# NARTF.net
KiCad netlist of a schematic drawn in EAGLE
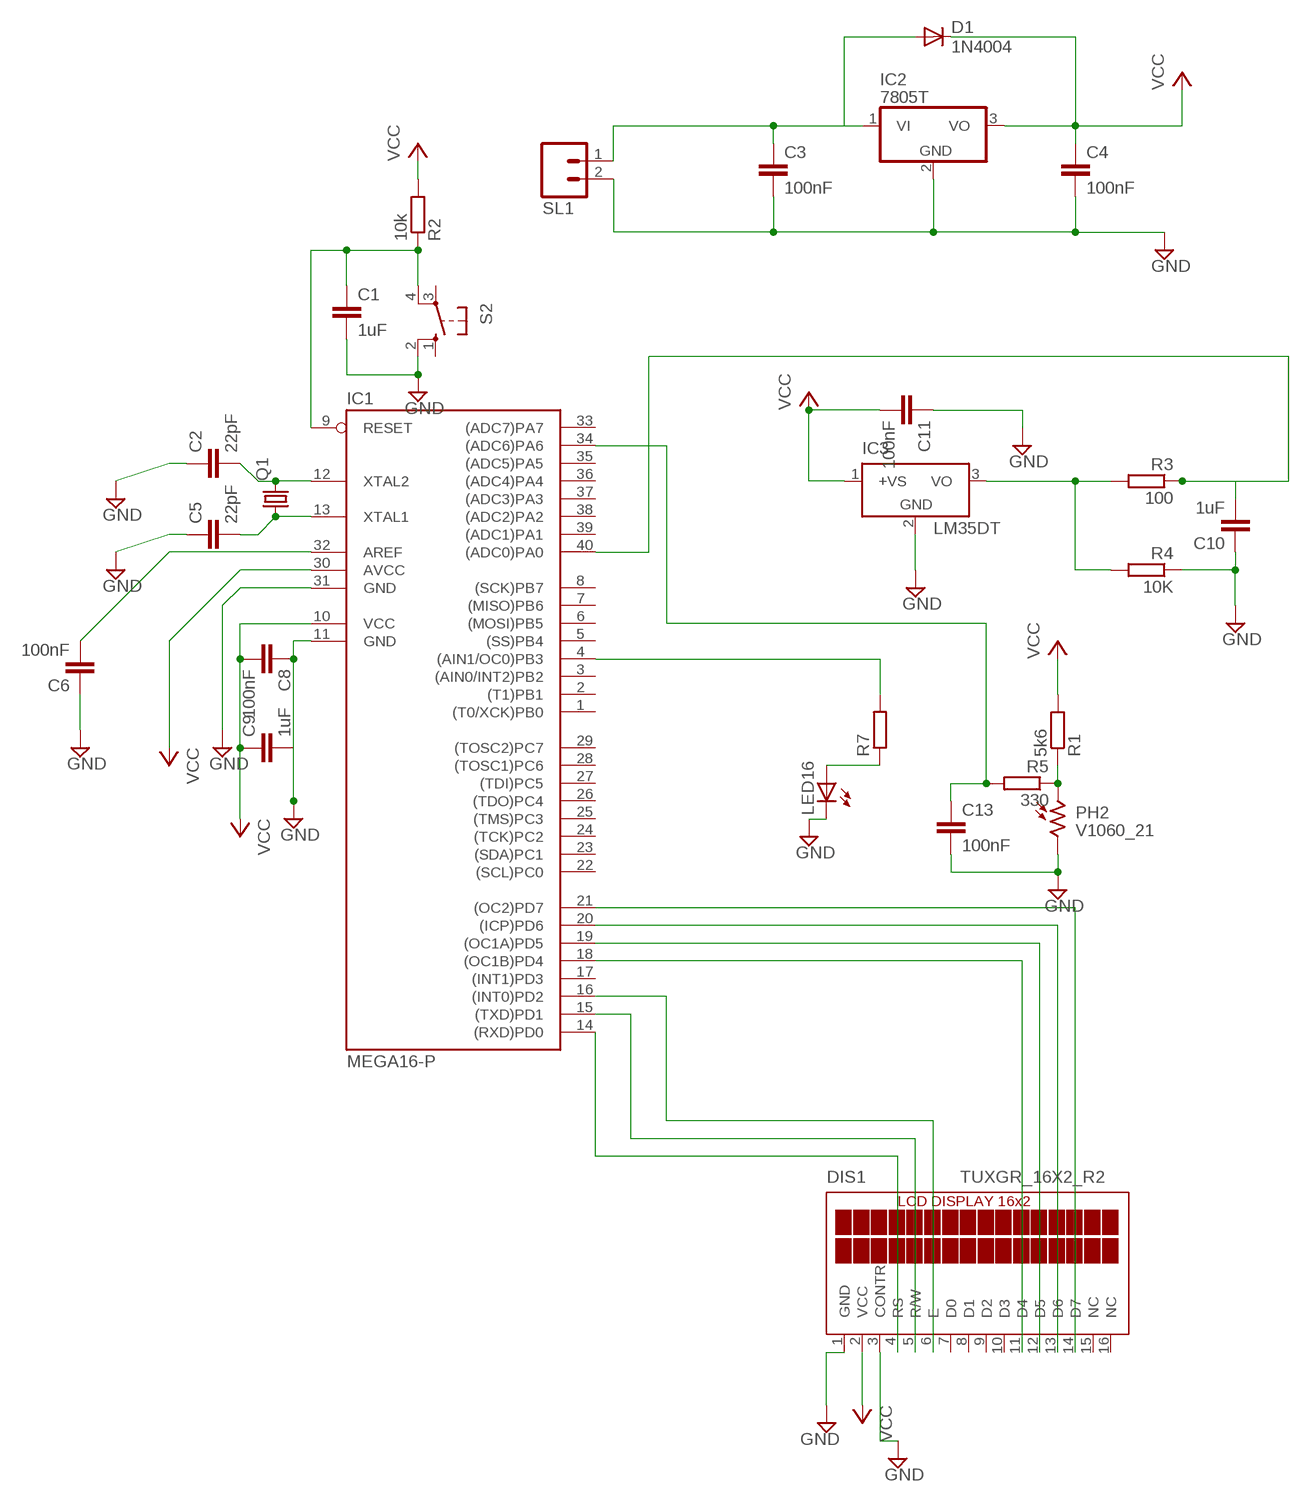
[diagram p0: schematic, sheet 1]

(export (version "E")
  (design (tool "Eeschema 10.0.6"))
  (components
    (comp (ref "C1")
      (value "1uF")
      (footprint "eagle-import:C025-025X050")
      (libsource (lib "eagle-import") (part "C-EU025-025X050"))
    )
    (comp (ref "C2")
      (value "22pF")
      (footprint "eagle-import:C025-025X050")
      (libsource (lib "eagle-import") (part "C-EU025-025X050"))
    )
    (comp (ref "C3")
      (value "100nF")
      (footprint "eagle-import:C025-025X050")
      (libsource (lib "eagle-import") (part "C-EU025-025X050"))
    )
    (comp (ref "C4")
      (value "100nF")
      (footprint "eagle-import:C025-025X050")
      (libsource (lib "eagle-import") (part "C-EU025-025X050"))
    )
    (comp (ref "C5")
      (value "22pF")
      (footprint "eagle-import:C025-025X050")
      (libsource (lib "eagle-import") (part "C-EU025-025X050"))
    )
    (comp (ref "C6")
      (value "100nF")
      (footprint "eagle-import:C025-025X050")
      (libsource (lib "eagle-import") (part "C-EU025-025X050"))
    )
    (comp (ref "C8")
      (value "100nF")
      (footprint "eagle-import:C025-025X050")
      (libsource (lib "eagle-import") (part "C-EU025-025X050"))
    )
    (comp (ref "C9")
      (value "1uF")
      (footprint "eagle-import:C025-025X050")
      (libsource (lib "eagle-import") (part "C-EU025-025X050"))
    )
    (comp (ref "C10")
      (value "1uF")
      (footprint "eagle-import:C025-025X050")
      (libsource (lib "eagle-import") (part "C-EU025-025X050"))
    )
    (comp (ref "C11")
      (value "100nF")
      (footprint "eagle-import:C025-025X050")
      (libsource (lib "eagle-import") (part "C-EU025-025X050"))
    )
    (comp (ref "C13")
      (value "100nF")
      (footprint "eagle-import:C025-025X050")
      (libsource (lib "eagle-import") (part "C-EU025-025X050"))
    )
    (comp (ref "D1")
      (value "1N4004")
      (footprint "eagle-import:DO41-10")
      (libsource (lib "eagle-import") (part "1N4004"))
    )
    (comp (ref "DIS1")
      (value "TUXGR_16X2_R2")
      (footprint "eagle-import:TUXGR_16X2_R2")
      (libsource (lib "eagle-import") (part "TUXGR_16X2_R2"))
    )
    (comp (ref "IC1")
      (value "MEGA16-P")
      (footprint "eagle-import:DIL40")
      (fields (field (name "MPN") "ATMEGA16-16PU"))
      (libsource (lib "eagle-import") (part "MEGA16-P"))
    )
    (comp (ref "IC2")
      (value "7805T")
      (footprint "eagle-import:TO220H")
      (libsource (lib "eagle-import") (part "78T05"))
    )
    (comp (ref "IC3")
      (value "LM35DT")
      (footprint "eagle-import:TO220V")
      (libsource (lib "eagle-import") (part "LM35DT"))
    )
    (comp (ref "LED16")
      (value "LED3MM")
      (footprint "eagle-import:LED3MM")
      (libsource (lib "eagle-import") (part "LED3MM"))
    )
    (comp (ref "PH2")
      (value "V1060_21")
      (footprint "eagle-import:TO-5_V10")
      (libsource (lib "eagle-import") (part "?1060V_21"))
    )
    (comp (ref "Q1")
      (value "CRYSTALHC49U70")
      (footprint "eagle-import:HC49U70")
      (libsource (lib "eagle-import") (part "CRYSTALHC49U70"))
    )
    (comp (ref "R1")
      (value "5k6")
      (footprint "eagle-import:0207_7")
      (libsource (lib "eagle-import") (part "R-EU_0207/7"))
    )
    (comp (ref "R2")
      (value "10k")
      (footprint "eagle-import:0207_7")
      (libsource (lib "eagle-import") (part "R-EU_0207/7"))
    )
    (comp (ref "R3")
      (value "100")
      (footprint "eagle-import:0207_7")
      (libsource (lib "eagle-import") (part "R-EU_0207/7"))
    )
    (comp (ref "R4")
      (value "10K")
      (footprint "eagle-import:0207_7")
      (libsource (lib "eagle-import") (part "R-EU_0207/7"))
    )
    (comp (ref "R5")
      (value "330")
      (footprint "eagle-import:0207_7")
      (libsource (lib "eagle-import") (part "R-EU_0207/7"))
    )
    (comp (ref "R7")
      (value "R-EU_0207/12")
      (footprint "eagle-import:0207_12")
      (libsource (lib "eagle-import") (part "rcl@1_R-EU_0207/12"))
    )
    (comp (ref "S2")
      (value "10-XX")
      (footprint "eagle-import:B3F-10XX")
      (fields (field (name "MPN") "B3F-1000"))
      (libsource (lib "eagle-import") (part "10-XX"))
    )
    (comp (ref "SL1")
      (value "M02")
      (footprint "eagle-import:02P")
      (libsource (lib "eagle-import") (part "M02"))
    )
  )
  (nets
    (net (code "1") (name "GND") (class "Default")
      (node (ref "C1") (pin "2") (pinfunction "2_2") (pintype "passive"))
      (node (ref "C10") (pin "1") (pinfunction "1_1") (pintype "passive"))
      (node (ref "C11") (pin "1") (pinfunction "1_1") (pintype "passive"))
      (node (ref "C13") (pin "2") (pinfunction "2_2") (pintype "passive"))
      (node (ref "C2") (pin "1") (pinfunction "1_1") (pintype "passive"))
      (node (ref "C3") (pin "2") (pinfunction "2_2") (pintype "passive"))
      (node (ref "C4") (pin "2") (pinfunction "2_2") (pintype "passive"))
      (node (ref "C5") (pin "1") (pinfunction "1_1") (pintype "passive"))
      (node (ref "C6") (pin "1") (pinfunction "1_1") (pintype "passive"))
      (node (ref "C8") (pin "1") (pinfunction "1_1") (pintype "passive"))
      (node (ref "C9") (pin "2") (pinfunction "2_2") (pintype "passive"))
      (node (ref "DIS1") (pin "1") (pinfunction "GND_1") (pintype "power_in"))
      (node (ref "DIS1") (pin "3") (pinfunction "CONTR_3") (pintype "input"))
      (node (ref "IC1") (pin "11") (pinfunction "GND_11") (pintype "power_in"))
      (node (ref "IC1") (pin "31") (pinfunction "GND_31") (pintype "power_in"))
      (node (ref "IC2") (pin "2") (pinfunction "GND_2") (pintype "passive"))
      (node (ref "IC3") (pin "2") (pinfunction "GND_2") (pintype "power_in"))
      (node (ref "LED16") (pin "K") (pinfunction "C_K") (pintype "passive"))
      (node (ref "PH2") (pin "2") (pinfunction "2_2") (pintype "passive"))
      (node (ref "R4") (pin "1") (pinfunction "1_1") (pintype "passive"))
      (node (ref "S2") (pin "2") (pinfunction "S1_2") (pintype "passive"))
      (node (ref "SL1") (pin "2") (pinfunction "2_2") (pintype "passive"))
    )
    (net (code "2") (name "Net-(DIS1-D4)") (class "Default")
      (node (ref "DIS1") (pin "11") (pinfunction "D4_11") (pintype "input"))
      (node (ref "IC1") (pin "18") (pinfunction "(OC1B)PD4_18") (pintype "bidirectional"))
    )
    (net (code "3") (name "Net-(DIS1-D5)") (class "Default")
      (node (ref "DIS1") (pin "12") (pinfunction "D5_12") (pintype "input"))
      (node (ref "IC1") (pin "19") (pinfunction "(OC1A)PD5_19") (pintype "bidirectional"))
    )
    (net (code "4") (name "Net-(DIS1-D6)") (class "Default")
      (node (ref "DIS1") (pin "13") (pinfunction "D6_13") (pintype "input"))
      (node (ref "IC1") (pin "20") (pinfunction "(ICP)PD6_20") (pintype "bidirectional"))
    )
    (net (code "5") (name "Net-(DIS1-D7)") (class "Default")
      (node (ref "DIS1") (pin "14") (pinfunction "D7_14") (pintype "input"))
      (node (ref "IC1") (pin "21") (pinfunction "(OC2)PD7_21") (pintype "bidirectional"))
    )
    (net (code "6") (name "Net-(DIS1-E)") (class "Default")
      (node (ref "DIS1") (pin "6") (pinfunction "E_6") (pintype "input"))
      (node (ref "IC1") (pin "16") (pinfunction "(INT0)PD2_16") (pintype "bidirectional"))
    )
    (net (code "7") (name "Net-(DIS1-RS)") (class "Default")
      (node (ref "DIS1") (pin "4") (pinfunction "RS_4") (pintype "input"))
      (node (ref "IC1") (pin "14") (pinfunction "(RXD)PD0_14") (pintype "bidirectional"))
    )
    (net (code "8") (name "Net-(DIS1-R{slash}W)") (class "Default")
      (node (ref "DIS1") (pin "5") (pinfunction "R/W_5") (pintype "input"))
      (node (ref "IC1") (pin "15") (pinfunction "(TXD)PD1_15") (pintype "bidirectional"))
    )
    (net (code "9") (name "Net-(IC1-(ADC0)PA0)") (class "Default")
      (node (ref "C10") (pin "2") (pinfunction "2_2") (pintype "passive"))
      (node (ref "IC1") (pin "40") (pinfunction "(ADC0)PA0_40") (pintype "bidirectional"))
      (node (ref "R3") (pin "1") (pinfunction "1_1") (pintype "passive"))
    )
    (net (code "10") (name "Net-(IC1-(ADC6)PA6)") (class "Default")
      (node (ref "C13") (pin "1") (pinfunction "1_1") (pintype "passive"))
      (node (ref "IC1") (pin "34") (pinfunction "(ADC6)PA6_34") (pintype "bidirectional"))
      (node (ref "R5") (pin "2") (pinfunction "2_2") (pintype "passive"))
    )
    (net (code "11") (name "Net-(IC1-(AIN1{slash}OC0)PB3)") (class "Default")
      (node (ref "IC1") (pin "4") (pinfunction "(AIN1/OC0)PB3_4") (pintype "bidirectional"))
      (node (ref "R7") (pin "2") (pinfunction "2_2") (pintype "passive"))
    )
    (net (code "12") (name "Net-(IC1-AREF)") (class "Default")
      (node (ref "C6") (pin "2") (pinfunction "2_2") (pintype "passive"))
      (node (ref "IC1") (pin "32") (pinfunction "AREF_32") (pintype "passive"))
    )
    (net (code "13") (name "Net-(IC1-RESET)") (class "Default")
      (node (ref "C1") (pin "1") (pinfunction "1_1") (pintype "passive"))
      (node (ref "IC1") (pin "9") (pinfunction "RESET_9") (pintype "input"))
      (node (ref "R2") (pin "1") (pinfunction "1_1") (pintype "passive"))
      (node (ref "S2") (pin "4") (pinfunction "P1_4") (pintype "passive"))
    )
    (net (code "14") (name "Net-(IC1-XTAL1)") (class "Default")
      (node (ref "C5") (pin "2") (pinfunction "2_2") (pintype "passive"))
      (node (ref "IC1") (pin "13") (pinfunction "XTAL1_13") (pintype "bidirectional"))
      (node (ref "Q1") (pin "1") (pinfunction "1_1") (pintype "passive"))
    )
    (net (code "15") (name "Net-(IC1-XTAL2)") (class "Default")
      (node (ref "C2") (pin "2") (pinfunction "2_2") (pintype "passive"))
      (node (ref "IC1") (pin "12") (pinfunction "XTAL2_12") (pintype "bidirectional"))
      (node (ref "Q1") (pin "2") (pinfunction "2_2") (pintype "passive"))
    )
    (net (code "16") (name "Net-(IC2-VI)") (class "Default")
      (node (ref "C3") (pin "1") (pinfunction "1_1") (pintype "passive"))
      (node (ref "D1") (pin "A") (pinfunction "A_A") (pintype "passive"))
      (node (ref "IC2") (pin "1") (pinfunction "VI_1") (pintype "input"))
      (node (ref "SL1") (pin "1") (pinfunction "1_1") (pintype "passive"))
    )
    (net (code "17") (name "Net-(IC3-VO)") (class "Default")
      (node (ref "IC3") (pin "3") (pinfunction "VO_3") (pintype "input"))
      (node (ref "R3") (pin "2") (pinfunction "2_2") (pintype "passive"))
      (node (ref "R4") (pin "2") (pinfunction "2_2") (pintype "passive"))
    )
    (net (code "18") (name "Net-(LED16-PadA)") (class "Default")
      (node (ref "LED16") (pin "A") (pinfunction "A_A") (pintype "passive"))
      (node (ref "R7") (pin "1") (pinfunction "1_1") (pintype "passive"))
    )
    (net (code "19") (name "Net-(PH2-Pad1)") (class "Default")
      (node (ref "PH2") (pin "1") (pinfunction "1_1") (pintype "passive"))
      (node (ref "R1") (pin "1") (pinfunction "1_1") (pintype "passive"))
      (node (ref "R5") (pin "1") (pinfunction "1_1") (pintype "passive"))
    )
    (net (code "20") (name "VCC") (class "Default")
      (node (ref "C11") (pin "2") (pinfunction "2_2") (pintype "passive"))
      (node (ref "C4") (pin "1") (pinfunction "1_1") (pintype "passive"))
      (node (ref "C8") (pin "2") (pinfunction "2_2") (pintype "passive"))
      (node (ref "C9") (pin "1") (pinfunction "1_1") (pintype "passive"))
      (node (ref "D1") (pin "C") (pinfunction "C_C") (pintype "passive"))
      (node (ref "DIS1") (pin "2") (pinfunction "VCC_2") (pintype "power_in"))
      (node (ref "IC1") (pin "10") (pinfunction "VCC_10") (pintype "power_in"))
      (node (ref "IC1") (pin "30") (pinfunction "AVCC_30") (pintype "power_in"))
      (node (ref "IC2") (pin "3") (pinfunction "VO_3") (pintype "passive"))
      (node (ref "IC3") (pin "1") (pinfunction "+VS_1") (pintype "input"))
      (node (ref "R1") (pin "2") (pinfunction "2_2") (pintype "passive"))
      (node (ref "R2") (pin "2") (pinfunction "2_2") (pintype "passive"))
    )
    (net (code "21") (name "unconnected-(DIS1-D0-Pad7)") (class "Default")
      (node (ref "DIS1") (pin "7") (pinfunction "D0_7") (pintype "input"))
    )
    (net (code "22") (name "unconnected-(DIS1-D1-Pad8)") (class "Default")
      (node (ref "DIS1") (pin "8") (pinfunction "D1_8") (pintype "input"))
    )
    (net (code "23") (name "unconnected-(DIS1-D2-Pad9)") (class "Default")
      (node (ref "DIS1") (pin "9") (pinfunction "D2_9") (pintype "input"))
    )
    (net (code "24") (name "unconnected-(DIS1-D3-Pad10)") (class "Default")
      (node (ref "DIS1") (pin "10") (pinfunction "D3_10") (pintype "input"))
    )
    (net (code "25") (name "unconnected-(DIS1-NC-Pad15)") (class "Default")
      (node (ref "DIS1") (pin "15") (pinfunction "NC_15") (pintype "no_connect"))
    )
    (net (code "26") (name "unconnected-(DIS1-NC-Pad16)") (class "Default")
      (node (ref "DIS1") (pin "16") (pinfunction "NC_16") (pintype "no_connect"))
    )
    (net (code "27") (name "unconnected-(IC1-(ADC1)PA1-Pad39)") (class "Default")
      (node (ref "IC1") (pin "39") (pinfunction "(ADC1)PA1_39") (pintype "bidirectional"))
    )
    (net (code "28") (name "unconnected-(IC1-(ADC2)PA2-Pad38)") (class "Default")
      (node (ref "IC1") (pin "38") (pinfunction "(ADC2)PA2_38") (pintype "bidirectional"))
    )
    (net (code "29") (name "unconnected-(IC1-(ADC3)PA3-Pad37)") (class "Default")
      (node (ref "IC1") (pin "37") (pinfunction "(ADC3)PA3_37") (pintype "bidirectional"))
    )
    (net (code "30") (name "unconnected-(IC1-(ADC4)PA4-Pad36)") (class "Default")
      (node (ref "IC1") (pin "36") (pinfunction "(ADC4)PA4_36") (pintype "bidirectional"))
    )
    (net (code "31") (name "unconnected-(IC1-(ADC5)PA5-Pad35)") (class "Default")
      (node (ref "IC1") (pin "35") (pinfunction "(ADC5)PA5_35") (pintype "bidirectional"))
    )
    (net (code "32") (name "unconnected-(IC1-(ADC7)PA7-Pad33)") (class "Default")
      (node (ref "IC1") (pin "33") (pinfunction "(ADC7)PA7_33") (pintype "bidirectional"))
    )
    (net (code "33") (name "unconnected-(IC1-(AIN0{slash}INT2)PB2-Pad3)") (class "Default")
      (node (ref "IC1") (pin "3") (pinfunction "(AIN0/INT2)PB2_3") (pintype "bidirectional"))
    )
    (net (code "34") (name "unconnected-(IC1-(INT1)PD3-Pad17)") (class "Default")
      (node (ref "IC1") (pin "17") (pinfunction "(INT1)PD3_17") (pintype "bidirectional"))
    )
    (net (code "35") (name "unconnected-(IC1-(MISO)PB6-Pad7)") (class "Default")
      (node (ref "IC1") (pin "7") (pinfunction "(MISO)PB6_7") (pintype "bidirectional"))
    )
    (net (code "36") (name "unconnected-(IC1-(MOSI)PB5-Pad6)") (class "Default")
      (node (ref "IC1") (pin "6") (pinfunction "(MOSI)PB5_6") (pintype "bidirectional"))
    )
    (net (code "37") (name "unconnected-(IC1-(SCK)PB7-Pad8)") (class "Default")
      (node (ref "IC1") (pin "8") (pinfunction "(SCK)PB7_8") (pintype "bidirectional"))
    )
    (net (code "38") (name "unconnected-(IC1-(SCL)PC0-Pad22)") (class "Default")
      (node (ref "IC1") (pin "22") (pinfunction "(SCL)PC0_22") (pintype "bidirectional"))
    )
    (net (code "39") (name "unconnected-(IC1-(SDA)PC1-Pad23)") (class "Default")
      (node (ref "IC1") (pin "23") (pinfunction "(SDA)PC1_23") (pintype "bidirectional"))
    )
    (net (code "40") (name "unconnected-(IC1-(SS)PB4-Pad5)") (class "Default")
      (node (ref "IC1") (pin "5") (pinfunction "(SS)PB4_5") (pintype "bidirectional"))
    )
    (net (code "41") (name "unconnected-(IC1-(T0{slash}XCK)PB0-Pad1)") (class "Default")
      (node (ref "IC1") (pin "1") (pinfunction "(T0/XCK)PB0_1") (pintype "bidirectional"))
    )
    (net (code "42") (name "unconnected-(IC1-(T1)PB1-Pad2)") (class "Default")
      (node (ref "IC1") (pin "2") (pinfunction "(T1)PB1_2") (pintype "bidirectional"))
    )
    (net (code "43") (name "unconnected-(IC1-(TCK)PC2-Pad24)") (class "Default")
      (node (ref "IC1") (pin "24") (pinfunction "(TCK)PC2_24") (pintype "bidirectional"))
    )
    (net (code "44") (name "unconnected-(IC1-(TDI)PC5-Pad27)") (class "Default")
      (node (ref "IC1") (pin "27") (pinfunction "(TDI)PC5_27") (pintype "bidirectional"))
    )
    (net (code "45") (name "unconnected-(IC1-(TDO)PC4-Pad26)") (class "Default")
      (node (ref "IC1") (pin "26") (pinfunction "(TDO)PC4_26") (pintype "bidirectional"))
    )
    (net (code "46") (name "unconnected-(IC1-(TMS)PC3-Pad25)") (class "Default")
      (node (ref "IC1") (pin "25") (pinfunction "(TMS)PC3_25") (pintype "bidirectional"))
    )
    (net (code "47") (name "unconnected-(IC1-(TOSC1)PC6-Pad28)") (class "Default")
      (node (ref "IC1") (pin "28") (pinfunction "(TOSC1)PC6_28") (pintype "bidirectional"))
    )
    (net (code "48") (name "unconnected-(IC1-(TOSC2)PC7-Pad29)") (class "Default")
      (node (ref "IC1") (pin "29") (pinfunction "(TOSC2)PC7_29") (pintype "bidirectional"))
    )
    (net (code "49") (name "unconnected-(S2-P-Pad3)") (class "Default")
      (node (ref "S2") (pin "3") (pinfunction "P_3") (pintype "passive"))
    )
    (net (code "50") (name "unconnected-(S2-S-Pad1)") (class "Default")
      (node (ref "S2") (pin "1") (pinfunction "S_1") (pintype "passive"))
    )
  )
)
